# 10-M2_GPS.net
KiCad netlist of a schematic drawn in Altium Designer
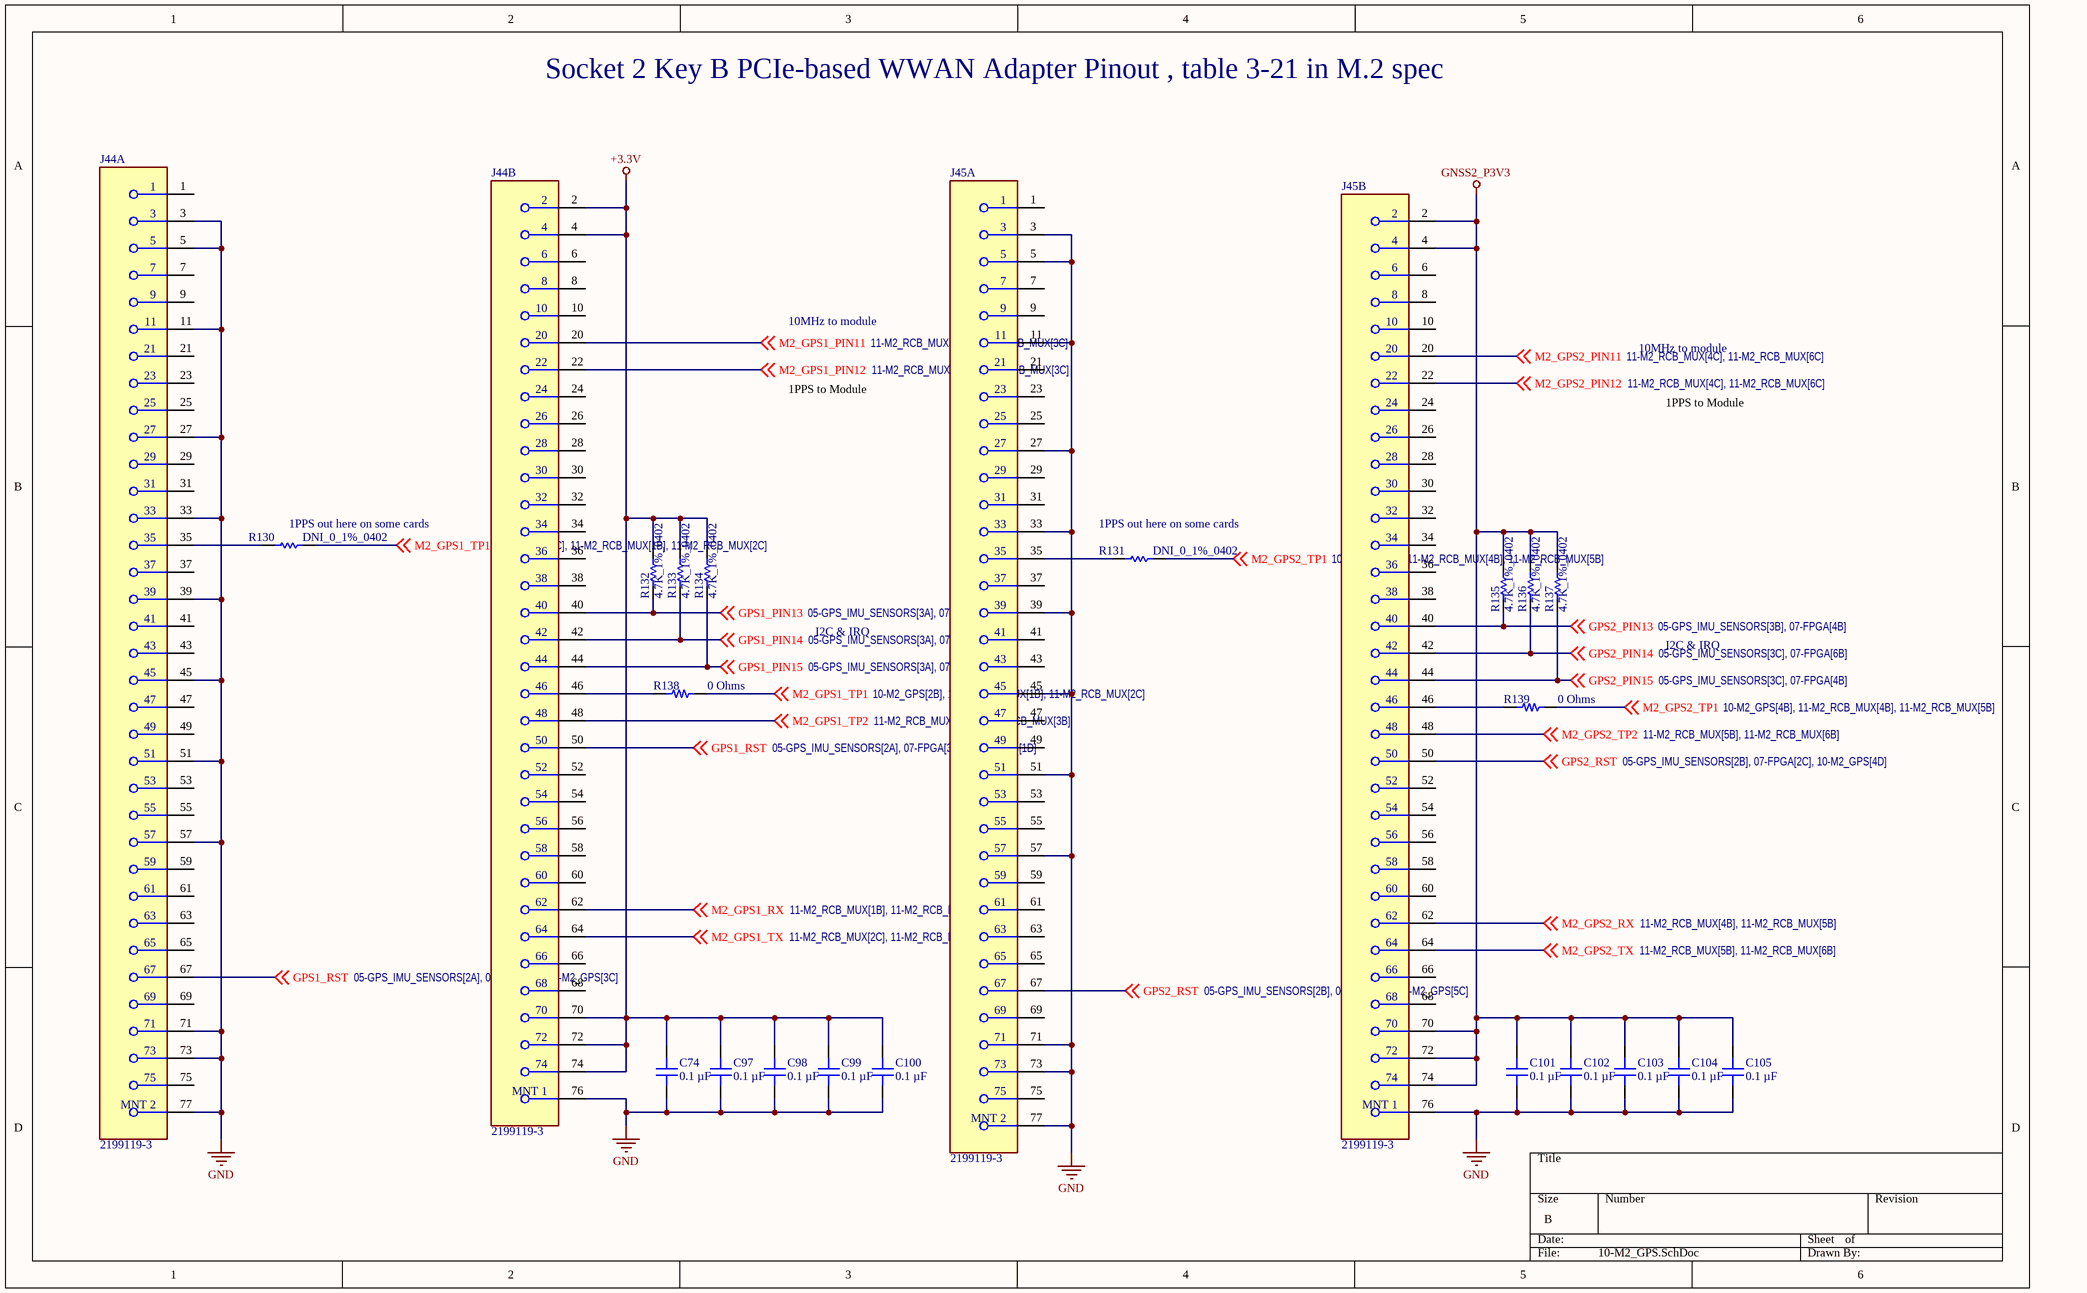
[diagram p0: 10-M2_GPS.SchDoc]

(export (version "E")
  (design (tool "Eeschema 10.0.6"))
  (components
    (comp (ref "C74")
      (value "0.1 µF")
      (footprint "CAP 0402_1005")
      (description "CAP CER 0.1UF 50V X7R 0402")
      (fields (field (name "TOLERANCE") "±10%") (field (name "PART NUMBER") "CC0402KRX7R9BB104"))
      (libsource (lib "Celestial Altium Library - altium_library") (part "Capacitor"))
    )
    (comp (ref "C97")
      (value "0.1 µF")
      (footprint "CAP 0402_1005")
      (description "CAP CER 0.1UF 50V X7R 0402")
      (fields (field (name "TOLERANCE") "±10%") (field (name "PART NUMBER") "CC0402KRX7R9BB104"))
      (libsource (lib "Celestial Altium Library - altium_library") (part "Capacitor"))
    )
    (comp (ref "C98")
      (value "0.1 µF")
      (footprint "CAP 0402_1005")
      (description "CAP CER 0.1UF 50V X7R 0402")
      (fields (field (name "TOLERANCE") "±10%") (field (name "PART NUMBER") "CC0402KRX7R9BB104"))
      (libsource (lib "Celestial Altium Library - altium_library") (part "Capacitor"))
    )
    (comp (ref "C99")
      (value "0.1 µF")
      (footprint "CAP 0402_1005")
      (description "CAP CER 0.1UF 50V X7R 0402")
      (fields (field (name "TOLERANCE") "±10%") (field (name "PART NUMBER") "CC0402KRX7R9BB104"))
      (libsource (lib "Celestial Altium Library - altium_library") (part "Capacitor"))
    )
    (comp (ref "C100")
      (value "0.1 µF")
      (footprint "CAP 0402_1005")
      (description "CAP CER 0.1UF 50V X7R 0402")
      (fields (field (name "TOLERANCE") "±10%") (field (name "PART NUMBER") "CC0402KRX7R9BB104"))
      (libsource (lib "Celestial Altium Library - altium_library") (part "Capacitor"))
    )
    (comp (ref "C101")
      (value "0.1 µF")
      (footprint "CAP 0402_1005")
      (description "CAP CER 0.1UF 50V X7R 0402")
      (fields (field (name "TOLERANCE") "±10%") (field (name "PART NUMBER") "CC0402KRX7R9BB104"))
      (libsource (lib "Celestial Altium Library - altium_library") (part "Capacitor"))
    )
    (comp (ref "C102")
      (value "0.1 µF")
      (footprint "CAP 0402_1005")
      (description "CAP CER 0.1UF 50V X7R 0402")
      (fields (field (name "TOLERANCE") "±10%") (field (name "PART NUMBER") "CC0402KRX7R9BB104"))
      (libsource (lib "Celestial Altium Library - altium_library") (part "Capacitor"))
    )
    (comp (ref "C103")
      (value "0.1 µF")
      (footprint "CAP 0402_1005")
      (description "CAP CER 0.1UF 50V X7R 0402")
      (fields (field (name "TOLERANCE") "±10%") (field (name "PART NUMBER") "CC0402KRX7R9BB104"))
      (libsource (lib "Celestial Altium Library - altium_library") (part "Capacitor"))
    )
    (comp (ref "C104")
      (value "0.1 µF")
      (footprint "CAP 0402_1005")
      (description "CAP CER 0.1UF 50V X7R 0402")
      (fields (field (name "TOLERANCE") "±10%") (field (name "PART NUMBER") "CC0402KRX7R9BB104"))
      (libsource (lib "Celestial Altium Library - altium_library") (part "Capacitor"))
    )
    (comp (ref "C105")
      (value "0.1 µF")
      (footprint "CAP 0402_1005")
      (description "CAP CER 0.1UF 50V X7R 0402")
      (fields (field (name "TOLERANCE") "±10%") (field (name "PART NUMBER") "CC0402KRX7R9BB104"))
      (libsource (lib "Celestial Altium Library - altium_library") (part "Capacitor"))
    )
    (comp (ref "J44")
      (value "2199119-3")
      (footprint "FP-2199119-3-MFG")
      (description "CONN M.2 FEMALE 67POS 0.020 GOLD")
      (libsource (lib "Altium Content Vault") (part "a14843ccfa78e5d0b739856168502fb"))
    )
    (comp (ref "J45")
      (value "2199119-3")
      (footprint "FP-2199119-3-MFG")
      (description "CONN M.2 FEMALE 67POS 0.020 GOLD")
      (libsource (lib "Altium Content Vault") (part "a14843ccfa78e5d0b739856168502fb"))
    )
    (comp (ref "R130")
      (value "DNI_0_1%_0402")
      (footprint "RESC1005X40X25LL05T05")
      (description "Chip Resistor, 0 Ohm, 0.1 W, -55 to 155 degC, 0402 (1005 Metric), RoHS, Tape and Reel")
      (fields (field (name "MANUFACTURER") "Panasonic") (field (name "TOLERANCE") "5%"))
      (libsource (lib "Altium Content Vault") (part "RES-2"))
    )
    (comp (ref "R131")
      (value "DNI_0_1%_0402")
      (footprint "RESC1005X40X25LL05T05")
      (description "Chip Resistor, 0 Ohm, 0.1 W, -55 to 155 degC, 0402 (1005 Metric), RoHS, Tape and Reel")
      (fields (field (name "MANUFACTURER") "Panasonic") (field (name "TOLERANCE") "5%"))
      (libsource (lib "Altium Content Vault") (part "RES-2"))
    )
    (comp (ref "R132")
      (value "4.7K_1%_0402")
      (footprint "RESC1005X40X25NL10T10")
      (fields (field (name "MANUFACTURER") "Bourns") (field (name "PART NUMBER") "CR0402-FX-4701GLF"))
      (libsource (lib "Altium Content Vault") (part "RES"))
    )
    (comp (ref "R133")
      (value "4.7K_1%_0402")
      (footprint "RESC1005X40X25NL10T10")
      (fields (field (name "MANUFACTURER") "Bourns") (field (name "PART NUMBER") "CR0402-FX-4701GLF"))
      (libsource (lib "Altium Content Vault") (part "RES"))
    )
    (comp (ref "R134")
      (value "4.7K_1%_0402")
      (footprint "RESC1005X40X25NL10T10")
      (fields (field (name "MANUFACTURER") "Bourns") (field (name "PART NUMBER") "CR0402-FX-4701GLF"))
      (libsource (lib "Altium Content Vault") (part "RES"))
    )
    (comp (ref "R135")
      (value "4.7K_1%_0402")
      (footprint "RESC1005X40X25NL10T10")
      (fields (field (name "MANUFACTURER") "Bourns") (field (name "PART NUMBER") "CR0402-FX-4701GLF"))
      (libsource (lib "Altium Content Vault") (part "RES"))
    )
    (comp (ref "R136")
      (value "4.7K_1%_0402")
      (footprint "RESC1005X40X25NL10T10")
      (fields (field (name "MANUFACTURER") "Bourns") (field (name "PART NUMBER") "CR0402-FX-4701GLF"))
      (libsource (lib "Altium Content Vault") (part "RES"))
    )
    (comp (ref "R137")
      (value "4.7K_1%_0402")
      (footprint "RESC1005X40X25NL10T10")
      (fields (field (name "MANUFACTURER") "Bourns") (field (name "PART NUMBER") "CR0402-FX-4701GLF"))
      (libsource (lib "Altium Content Vault") (part "RES"))
    )
    (comp (ref "R138")
      (value "0 Ohms")
      (footprint "YAGEO RES 0402_1005")
      (description "RES 0 OHM JUMPER 1/16W 0402")
      (fields (field (name "MANUFACTURER") "Yageo") (field (name "TOLERANCE") "Jumper"))
      (libsource (lib "Celestial Altium Library - altium_library") (part "Resistor"))
    )
    (comp (ref "R139")
      (value "0 Ohms")
      (footprint "YAGEO RES 0402_1005")
      (description "RES 0 OHM JUMPER 1/16W 0402")
      (fields (field (name "MANUFACTURER") "Yageo") (field (name "TOLERANCE") "Jumper"))
      (libsource (lib "Celestial Altium Library - altium_library") (part "Resistor"))
    )
  )
  (nets
    (net (code "1") (name "+3.3V") (class "Default")
      (node (ref "C100") (pin "1") (pinfunction "1_1") (pintype "passive"))
      (node (ref "C74") (pin "1") (pinfunction "1_1") (pintype "passive"))
      (node (ref "C97") (pin "1") (pinfunction "1_1") (pintype "passive"))
      (node (ref "C98") (pin "1") (pinfunction "1_1") (pintype "passive"))
      (node (ref "C99") (pin "1") (pinfunction "1_1") (pintype "passive"))
      (node (ref "J44") (pin "2") (pinfunction "2_2") (pintype "passive"))
      (node (ref "J44") (pin "4") (pinfunction "4_4") (pintype "passive"))
      (node (ref "J44") (pin "70") (pinfunction "70_70") (pintype "passive"))
      (node (ref "J44") (pin "72") (pinfunction "72_72") (pintype "passive"))
      (node (ref "J44") (pin "74") (pinfunction "74_74") (pintype "passive"))
      (node (ref "R132") (pin "2") (pinfunction "2_2") (pintype "passive"))
      (node (ref "R133") (pin "2") (pinfunction "2_2") (pintype "passive"))
      (node (ref "R134") (pin "2") (pinfunction "2_2") (pintype "passive"))
    )
    (net (code "2") (name "GND") (class "Default")
      (node (ref "C100") (pin "2") (pinfunction "2_2") (pintype "passive"))
      (node (ref "C101") (pin "2") (pinfunction "2_2") (pintype "passive"))
      (node (ref "C102") (pin "2") (pinfunction "2_2") (pintype "passive"))
      (node (ref "C103") (pin "2") (pinfunction "2_2") (pintype "passive"))
      (node (ref "C104") (pin "2") (pinfunction "2_2") (pintype "passive"))
      (node (ref "C105") (pin "2") (pinfunction "2_2") (pintype "passive"))
      (node (ref "C74") (pin "2") (pinfunction "2_2") (pintype "passive"))
      (node (ref "C97") (pin "2") (pinfunction "2_2") (pintype "passive"))
      (node (ref "C98") (pin "2") (pinfunction "2_2") (pintype "passive"))
      (node (ref "C99") (pin "2") (pinfunction "2_2") (pintype "passive"))
      (node (ref "J44") (pin "11") (pinfunction "11_11") (pintype "passive"))
      (node (ref "J44") (pin "27") (pinfunction "27_27") (pintype "passive"))
      (node (ref "J44") (pin "3") (pinfunction "3_3") (pintype "passive"))
      (node (ref "J44") (pin "33") (pinfunction "33_33") (pintype "passive"))
      (node (ref "J44") (pin "39") (pinfunction "39_39") (pintype "passive"))
      (node (ref "J44") (pin "45") (pinfunction "45_45") (pintype "passive"))
      (node (ref "J44") (pin "5") (pinfunction "5_5") (pintype "passive"))
      (node (ref "J44") (pin "51") (pinfunction "51_51") (pintype "passive"))
      (node (ref "J44") (pin "57") (pinfunction "57_57") (pintype "passive"))
      (node (ref "J44") (pin "71") (pinfunction "71_71") (pintype "passive"))
      (node (ref "J44") (pin "73") (pinfunction "73_73") (pintype "passive"))
      (node (ref "J44") (pin "76") (pinfunction "MNT_1_76") (pintype "passive"))
      (node (ref "J44") (pin "77") (pinfunction "MNT_2_77") (pintype "passive"))
      (node (ref "J45") (pin "11") (pinfunction "11_11") (pintype "passive"))
      (node (ref "J45") (pin "27") (pinfunction "27_27") (pintype "passive"))
      (node (ref "J45") (pin "3") (pinfunction "3_3") (pintype "passive"))
      (node (ref "J45") (pin "33") (pinfunction "33_33") (pintype "passive"))
      (node (ref "J45") (pin "39") (pinfunction "39_39") (pintype "passive"))
      (node (ref "J45") (pin "45") (pinfunction "45_45") (pintype "passive"))
      (node (ref "J45") (pin "5") (pinfunction "5_5") (pintype "passive"))
      (node (ref "J45") (pin "51") (pinfunction "51_51") (pintype "passive"))
      (node (ref "J45") (pin "57") (pinfunction "57_57") (pintype "passive"))
      (node (ref "J45") (pin "71") (pinfunction "71_71") (pintype "passive"))
      (node (ref "J45") (pin "73") (pinfunction "73_73") (pintype "passive"))
      (node (ref "J45") (pin "76") (pinfunction "MNT_1_76") (pintype "passive"))
      (node (ref "J45") (pin "77") (pinfunction "MNT_2_77") (pintype "passive"))
    )
    (net (code "3") (name "GNSS2_P3V3") (class "Default")
      (node (ref "C101") (pin "1") (pinfunction "1_1") (pintype "passive"))
      (node (ref "C102") (pin "1") (pinfunction "1_1") (pintype "passive"))
      (node (ref "C103") (pin "1") (pinfunction "1_1") (pintype "passive"))
      (node (ref "C104") (pin "1") (pinfunction "1_1") (pintype "passive"))
      (node (ref "C105") (pin "1") (pinfunction "1_1") (pintype "passive"))
      (node (ref "J45") (pin "2") (pinfunction "2_2") (pintype "passive"))
      (node (ref "J45") (pin "4") (pinfunction "4_4") (pintype "passive"))
      (node (ref "J45") (pin "70") (pinfunction "70_70") (pintype "passive"))
      (node (ref "J45") (pin "72") (pinfunction "72_72") (pintype "passive"))
      (node (ref "J45") (pin "74") (pinfunction "74_74") (pintype "passive"))
      (node (ref "R135") (pin "2") (pinfunction "2_2") (pintype "passive"))
      (node (ref "R136") (pin "2") (pinfunction "2_2") (pintype "passive"))
      (node (ref "R137") (pin "2") (pinfunction "2_2") (pintype "passive"))
    )
    (net (code "4") (name "GPS1_PIN13") (class "Default")
      (node (ref "J44") (pin "40") (pinfunction "40_40") (pintype "passive"))
      (node (ref "R132") (pin "1") (pinfunction "1_1") (pintype "passive"))
    )
    (net (code "5") (name "GPS1_PIN14") (class "Default")
      (node (ref "J44") (pin "42") (pinfunction "42_42") (pintype "passive"))
      (node (ref "R133") (pin "1") (pinfunction "1_1") (pintype "passive"))
    )
    (net (code "6") (name "GPS1_PIN15") (class "Default")
      (node (ref "J44") (pin "44") (pinfunction "44_44") (pintype "passive"))
      (node (ref "R134") (pin "1") (pinfunction "1_1") (pintype "passive"))
    )
    (net (code "7") (name "GPS1_RST") (class "Default")
      (node (ref "J44") (pin "50") (pinfunction "50_50") (pintype "passive"))
      (node (ref "J44") (pin "67") (pinfunction "67_67") (pintype "passive"))
    )
    (net (code "8") (name "GPS2_PIN13") (class "Default")
      (node (ref "J45") (pin "40") (pinfunction "40_40") (pintype "passive"))
      (node (ref "R135") (pin "1") (pinfunction "1_1") (pintype "passive"))
    )
    (net (code "9") (name "GPS2_PIN14") (class "Default")
      (node (ref "J45") (pin "42") (pinfunction "42_42") (pintype "passive"))
      (node (ref "R136") (pin "1") (pinfunction "1_1") (pintype "passive"))
    )
    (net (code "10") (name "GPS2_PIN15") (class "Default")
      (node (ref "J45") (pin "44") (pinfunction "44_44") (pintype "passive"))
      (node (ref "R137") (pin "1") (pinfunction "1_1") (pintype "passive"))
    )
    (net (code "11") (name "GPS2_RST") (class "Default")
      (node (ref "J45") (pin "50") (pinfunction "50_50") (pintype "passive"))
      (node (ref "J45") (pin "67") (pinfunction "67_67") (pintype "passive"))
    )
    (net (code "12") (name "M2_GPS1_PIN11") (class "Default")
      (node (ref "J44") (pin "20") (pinfunction "20_20") (pintype "passive"))
    )
    (net (code "13") (name "M2_GPS1_PIN12") (class "Default")
      (node (ref "J44") (pin "22") (pinfunction "22_22") (pintype "passive"))
    )
    (net (code "14") (name "M2_GPS1_RX") (class "Default")
      (node (ref "J44") (pin "62") (pinfunction "62_62") (pintype "passive"))
    )
    (net (code "15") (name "M2_GPS1_TP1") (class "Default")
      (node (ref "R130") (pin "2") (pinfunction "2_2") (pintype "passive"))
      (node (ref "R138") (pin "2") (pinfunction "2_2") (pintype "passive"))
    )
    (net (code "16") (name "M2_GPS1_TP2") (class "Default")
      (node (ref "J44") (pin "48") (pinfunction "48_48") (pintype "passive"))
    )
    (net (code "17") (name "M2_GPS1_TX") (class "Default")
      (node (ref "J44") (pin "64") (pinfunction "64_64") (pintype "passive"))
    )
    (net (code "18") (name "M2_GPS2_PIN11") (class "Default")
      (node (ref "J45") (pin "20") (pinfunction "20_20") (pintype "passive"))
    )
    (net (code "19") (name "M2_GPS2_PIN12") (class "Default")
      (node (ref "J45") (pin "22") (pinfunction "22_22") (pintype "passive"))
    )
    (net (code "20") (name "M2_GPS2_RX") (class "Default")
      (node (ref "J45") (pin "62") (pinfunction "62_62") (pintype "passive"))
    )
    (net (code "21") (name "M2_GPS2_TP1") (class "Default")
      (node (ref "R131") (pin "2") (pinfunction "2_2") (pintype "passive"))
      (node (ref "R139") (pin "2") (pinfunction "2_2") (pintype "passive"))
    )
    (net (code "22") (name "M2_GPS2_TP2") (class "Default")
      (node (ref "J45") (pin "48") (pinfunction "48_48") (pintype "passive"))
    )
    (net (code "23") (name "M2_GPS2_TX") (class "Default")
      (node (ref "J45") (pin "64") (pinfunction "64_64") (pintype "passive"))
    )
    (net (code "24") (name "Net-(J44-Pad35)") (class "Default")
      (node (ref "J44") (pin "35") (pinfunction "35_35") (pintype "passive"))
      (node (ref "R130") (pin "1") (pinfunction "1_1") (pintype "passive"))
    )
    (net (code "25") (name "Net-(J44-Pad46)") (class "Default")
      (node (ref "J44") (pin "46") (pinfunction "46_46") (pintype "passive"))
      (node (ref "R138") (pin "1") (pinfunction "1_1") (pintype "passive"))
    )
    (net (code "26") (name "Net-(J45-Pad35)") (class "Default")
      (node (ref "J45") (pin "35") (pinfunction "35_35") (pintype "passive"))
      (node (ref "R131") (pin "1") (pinfunction "1_1") (pintype "passive"))
    )
    (net (code "27") (name "Net-(J45-Pad46)") (class "Default")
      (node (ref "J45") (pin "46") (pinfunction "46_46") (pintype "passive"))
      (node (ref "R139") (pin "1") (pinfunction "1_1") (pintype "passive"))
    )
    (net (code "28") (name "unconnected-(J44-Pad1)") (class "Default")
      (node (ref "J44") (pin "1") (pinfunction "1_1") (pintype "passive"))
    )
    (net (code "29") (name "unconnected-(J44-Pad6)") (class "Default")
      (node (ref "J44") (pin "6") (pinfunction "6_6") (pintype "passive"))
    )
    (net (code "30") (name "unconnected-(J44-Pad7)") (class "Default")
      (node (ref "J44") (pin "7") (pinfunction "7_7") (pintype "passive"))
    )
    (net (code "31") (name "unconnected-(J44-Pad8)") (class "Default")
      (node (ref "J44") (pin "8") (pinfunction "8_8") (pintype "passive"))
    )
    (net (code "32") (name "unconnected-(J44-Pad9)") (class "Default")
      (node (ref "J44") (pin "9") (pinfunction "9_9") (pintype "passive"))
    )
    (net (code "33") (name "unconnected-(J44-Pad10)") (class "Default")
      (node (ref "J44") (pin "10") (pinfunction "10_10") (pintype "passive"))
    )
    (net (code "34") (name "unconnected-(J44-Pad21)") (class "Default")
      (node (ref "J44") (pin "21") (pinfunction "21_21") (pintype "passive"))
    )
    (net (code "35") (name "unconnected-(J44-Pad23)") (class "Default")
      (node (ref "J44") (pin "23") (pinfunction "23_23") (pintype "passive"))
    )
    (net (code "36") (name "unconnected-(J44-Pad24)") (class "Default")
      (node (ref "J44") (pin "24") (pinfunction "24_24") (pintype "passive"))
    )
    (net (code "37") (name "unconnected-(J44-Pad25)") (class "Default")
      (node (ref "J44") (pin "25") (pinfunction "25_25") (pintype "passive"))
    )
    (net (code "38") (name "unconnected-(J44-Pad26)") (class "Default")
      (node (ref "J44") (pin "26") (pinfunction "26_26") (pintype "passive"))
    )
    (net (code "39") (name "unconnected-(J44-Pad28)") (class "Default")
      (node (ref "J44") (pin "28") (pinfunction "28_28") (pintype "passive"))
    )
    (net (code "40") (name "unconnected-(J44-Pad29)") (class "Default")
      (node (ref "J44") (pin "29") (pinfunction "29_29") (pintype "passive"))
    )
    (net (code "41") (name "unconnected-(J44-Pad30)") (class "Default")
      (node (ref "J44") (pin "30") (pinfunction "30_30") (pintype "passive"))
    )
    (net (code "42") (name "unconnected-(J44-Pad31)") (class "Default")
      (node (ref "J44") (pin "31") (pinfunction "31_31") (pintype "passive"))
    )
    (net (code "43") (name "unconnected-(J44-Pad32)") (class "Default")
      (node (ref "J44") (pin "32") (pinfunction "32_32") (pintype "passive"))
    )
    (net (code "44") (name "unconnected-(J44-Pad34)") (class "Default")
      (node (ref "J44") (pin "34") (pinfunction "34_34") (pintype "passive"))
    )
    (net (code "45") (name "unconnected-(J44-Pad36)") (class "Default")
      (node (ref "J44") (pin "36") (pinfunction "36_36") (pintype "passive"))
    )
    (net (code "46") (name "unconnected-(J44-Pad37)") (class "Default")
      (node (ref "J44") (pin "37") (pinfunction "37_37") (pintype "passive"))
    )
    (net (code "47") (name "unconnected-(J44-Pad38)") (class "Default")
      (node (ref "J44") (pin "38") (pinfunction "38_38") (pintype "passive"))
    )
    (net (code "48") (name "unconnected-(J44-Pad41)") (class "Default")
      (node (ref "J44") (pin "41") (pinfunction "41_41") (pintype "passive"))
    )
    (net (code "49") (name "unconnected-(J44-Pad43)") (class "Default")
      (node (ref "J44") (pin "43") (pinfunction "43_43") (pintype "passive"))
    )
    (net (code "50") (name "unconnected-(J44-Pad47)") (class "Default")
      (node (ref "J44") (pin "47") (pinfunction "47_47") (pintype "passive"))
    )
    (net (code "51") (name "unconnected-(J44-Pad49)") (class "Default")
      (node (ref "J44") (pin "49") (pinfunction "49_49") (pintype "passive"))
    )
    (net (code "52") (name "unconnected-(J44-Pad52)") (class "Default")
      (node (ref "J44") (pin "52") (pinfunction "52_52") (pintype "passive"))
    )
    (net (code "53") (name "unconnected-(J44-Pad53)") (class "Default")
      (node (ref "J44") (pin "53") (pinfunction "53_53") (pintype "passive"))
    )
    (net (code "54") (name "unconnected-(J44-Pad54)") (class "Default")
      (node (ref "J44") (pin "54") (pinfunction "54_54") (pintype "passive"))
    )
    (net (code "55") (name "unconnected-(J44-Pad55)") (class "Default")
      (node (ref "J44") (pin "55") (pinfunction "55_55") (pintype "passive"))
    )
    (net (code "56") (name "unconnected-(J44-Pad56)") (class "Default")
      (node (ref "J44") (pin "56") (pinfunction "56_56") (pintype "passive"))
    )
    (net (code "57") (name "unconnected-(J44-Pad58)") (class "Default")
      (node (ref "J44") (pin "58") (pinfunction "58_58") (pintype "passive"))
    )
    (net (code "58") (name "unconnected-(J44-Pad59)") (class "Default")
      (node (ref "J44") (pin "59") (pinfunction "59_59") (pintype "passive"))
    )
    (net (code "59") (name "unconnected-(J44-Pad60)") (class "Default")
      (node (ref "J44") (pin "60") (pinfunction "60_60") (pintype "passive"))
    )
    (net (code "60") (name "unconnected-(J44-Pad61)") (class "Default")
      (node (ref "J44") (pin "61") (pinfunction "61_61") (pintype "passive"))
    )
    (net (code "61") (name "unconnected-(J44-Pad63)") (class "Default")
      (node (ref "J44") (pin "63") (pinfunction "63_63") (pintype "passive"))
    )
    (net (code "62") (name "unconnected-(J44-Pad65)") (class "Default")
      (node (ref "J44") (pin "65") (pinfunction "65_65") (pintype "passive"))
    )
    (net (code "63") (name "unconnected-(J44-Pad66)") (class "Default")
      (node (ref "J44") (pin "66") (pinfunction "66_66") (pintype "passive"))
    )
    (net (code "64") (name "unconnected-(J44-Pad68)") (class "Default")
      (node (ref "J44") (pin "68") (pinfunction "68_68") (pintype "passive"))
    )
    (net (code "65") (name "unconnected-(J44-Pad69)") (class "Default")
      (node (ref "J44") (pin "69") (pinfunction "69_69") (pintype "passive"))
    )
    (net (code "66") (name "unconnected-(J44-Pad75)") (class "Default")
      (node (ref "J44") (pin "75") (pinfunction "75_75") (pintype "passive"))
    )
    (net (code "67") (name "unconnected-(J45-Pad1)") (class "Default")
      (node (ref "J45") (pin "1") (pinfunction "1_1") (pintype "passive"))
    )
    (net (code "68") (name "unconnected-(J45-Pad6)") (class "Default")
      (node (ref "J45") (pin "6") (pinfunction "6_6") (pintype "passive"))
    )
    (net (code "69") (name "unconnected-(J45-Pad7)") (class "Default")
      (node (ref "J45") (pin "7") (pinfunction "7_7") (pintype "passive"))
    )
    (net (code "70") (name "unconnected-(J45-Pad8)") (class "Default")
      (node (ref "J45") (pin "8") (pinfunction "8_8") (pintype "passive"))
    )
    (net (code "71") (name "unconnected-(J45-Pad9)") (class "Default")
      (node (ref "J45") (pin "9") (pinfunction "9_9") (pintype "passive"))
    )
    (net (code "72") (name "unconnected-(J45-Pad10)") (class "Default")
      (node (ref "J45") (pin "10") (pinfunction "10_10") (pintype "passive"))
    )
    (net (code "73") (name "unconnected-(J45-Pad21)") (class "Default")
      (node (ref "J45") (pin "21") (pinfunction "21_21") (pintype "passive"))
    )
    (net (code "74") (name "unconnected-(J45-Pad23)") (class "Default")
      (node (ref "J45") (pin "23") (pinfunction "23_23") (pintype "passive"))
    )
    (net (code "75") (name "unconnected-(J45-Pad24)") (class "Default")
      (node (ref "J45") (pin "24") (pinfunction "24_24") (pintype "passive"))
    )
    (net (code "76") (name "unconnected-(J45-Pad25)") (class "Default")
      (node (ref "J45") (pin "25") (pinfunction "25_25") (pintype "passive"))
    )
    (net (code "77") (name "unconnected-(J45-Pad26)") (class "Default")
      (node (ref "J45") (pin "26") (pinfunction "26_26") (pintype "passive"))
    )
    (net (code "78") (name "unconnected-(J45-Pad28)") (class "Default")
      (node (ref "J45") (pin "28") (pinfunction "28_28") (pintype "passive"))
    )
    (net (code "79") (name "unconnected-(J45-Pad29)") (class "Default")
      (node (ref "J45") (pin "29") (pinfunction "29_29") (pintype "passive"))
    )
    (net (code "80") (name "unconnected-(J45-Pad30)") (class "Default")
      (node (ref "J45") (pin "30") (pinfunction "30_30") (pintype "passive"))
    )
    (net (code "81") (name "unconnected-(J45-Pad31)") (class "Default")
      (node (ref "J45") (pin "31") (pinfunction "31_31") (pintype "passive"))
    )
    (net (code "82") (name "unconnected-(J45-Pad32)") (class "Default")
      (node (ref "J45") (pin "32") (pinfunction "32_32") (pintype "passive"))
    )
    (net (code "83") (name "unconnected-(J45-Pad34)") (class "Default")
      (node (ref "J45") (pin "34") (pinfunction "34_34") (pintype "passive"))
    )
    (net (code "84") (name "unconnected-(J45-Pad36)") (class "Default")
      (node (ref "J45") (pin "36") (pinfunction "36_36") (pintype "passive"))
    )
    (net (code "85") (name "unconnected-(J45-Pad37)") (class "Default")
      (node (ref "J45") (pin "37") (pinfunction "37_37") (pintype "passive"))
    )
    (net (code "86") (name "unconnected-(J45-Pad38)") (class "Default")
      (node (ref "J45") (pin "38") (pinfunction "38_38") (pintype "passive"))
    )
    (net (code "87") (name "unconnected-(J45-Pad41)") (class "Default")
      (node (ref "J45") (pin "41") (pinfunction "41_41") (pintype "passive"))
    )
    (net (code "88") (name "unconnected-(J45-Pad43)") (class "Default")
      (node (ref "J45") (pin "43") (pinfunction "43_43") (pintype "passive"))
    )
    (net (code "89") (name "unconnected-(J45-Pad47)") (class "Default")
      (node (ref "J45") (pin "47") (pinfunction "47_47") (pintype "passive"))
    )
    (net (code "90") (name "unconnected-(J45-Pad49)") (class "Default")
      (node (ref "J45") (pin "49") (pinfunction "49_49") (pintype "passive"))
    )
    (net (code "91") (name "unconnected-(J45-Pad52)") (class "Default")
      (node (ref "J45") (pin "52") (pinfunction "52_52") (pintype "passive"))
    )
    (net (code "92") (name "unconnected-(J45-Pad53)") (class "Default")
      (node (ref "J45") (pin "53") (pinfunction "53_53") (pintype "passive"))
    )
    (net (code "93") (name "unconnected-(J45-Pad54)") (class "Default")
      (node (ref "J45") (pin "54") (pinfunction "54_54") (pintype "passive"))
    )
    (net (code "94") (name "unconnected-(J45-Pad55)") (class "Default")
      (node (ref "J45") (pin "55") (pinfunction "55_55") (pintype "passive"))
    )
    (net (code "95") (name "unconnected-(J45-Pad56)") (class "Default")
      (node (ref "J45") (pin "56") (pinfunction "56_56") (pintype "passive"))
    )
    (net (code "96") (name "unconnected-(J45-Pad58)") (class "Default")
      (node (ref "J45") (pin "58") (pinfunction "58_58") (pintype "passive"))
    )
    (net (code "97") (name "unconnected-(J45-Pad59)") (class "Default")
      (node (ref "J45") (pin "59") (pinfunction "59_59") (pintype "passive"))
    )
    (net (code "98") (name "unconnected-(J45-Pad60)") (class "Default")
      (node (ref "J45") (pin "60") (pinfunction "60_60") (pintype "passive"))
    )
    (net (code "99") (name "unconnected-(J45-Pad61)") (class "Default")
      (node (ref "J45") (pin "61") (pinfunction "61_61") (pintype "passive"))
    )
    (net (code "100") (name "unconnected-(J45-Pad63)") (class "Default")
      (node (ref "J45") (pin "63") (pinfunction "63_63") (pintype "passive"))
    )
    (net (code "101") (name "unconnected-(J45-Pad65)") (class "Default")
      (node (ref "J45") (pin "65") (pinfunction "65_65") (pintype "passive"))
    )
    (net (code "102") (name "unconnected-(J45-Pad66)") (class "Default")
      (node (ref "J45") (pin "66") (pinfunction "66_66") (pintype "passive"))
    )
    (net (code "103") (name "unconnected-(J45-Pad68)") (class "Default")
      (node (ref "J45") (pin "68") (pinfunction "68_68") (pintype "passive"))
    )
    (net (code "104") (name "unconnected-(J45-Pad69)") (class "Default")
      (node (ref "J45") (pin "69") (pinfunction "69_69") (pintype "passive"))
    )
    (net (code "105") (name "unconnected-(J45-Pad75)") (class "Default")
      (node (ref "J45") (pin "75") (pinfunction "75_75") (pintype "passive"))
    )
  )
)
